# main_board.net
KiCad netlist of a schematic drawn in Altium Designer
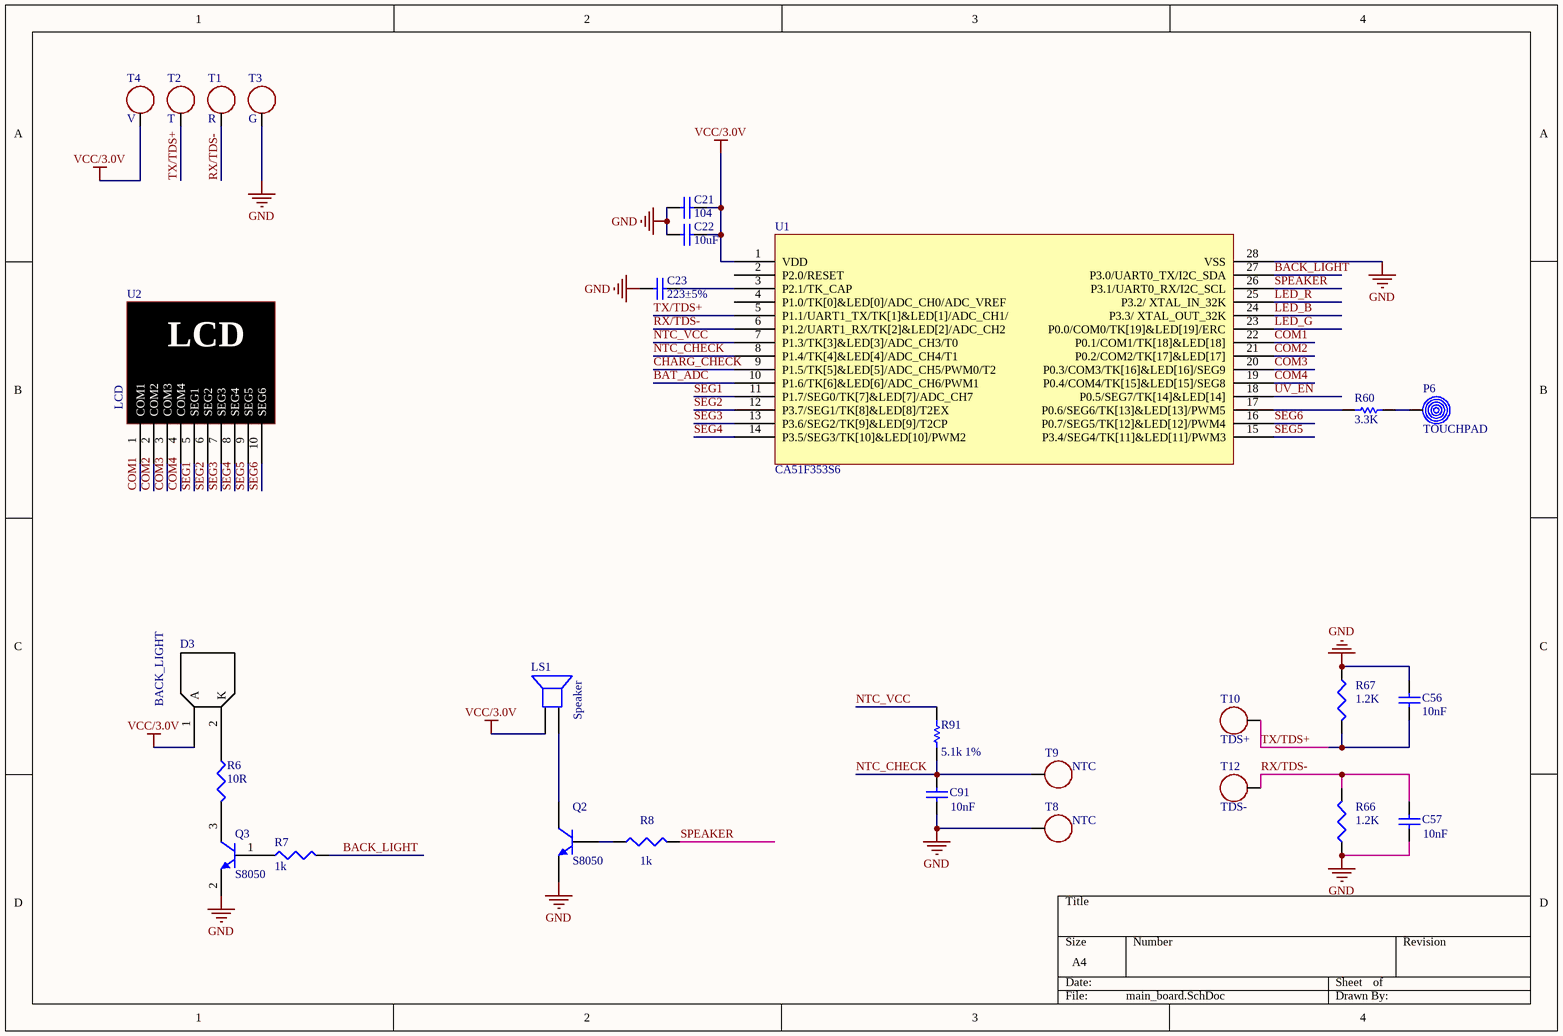
[diagram p0: main_board.SchDoc]

(export (version "E")
  (design (tool "Eeschema 10.0.6"))
  (components
    (comp (ref "C21")
      (value "104")
      (footprint "C0402")
      (description "电容")
      (fields (field (name "Comment") "Cap") (field (name "PUBLISHER") "Altium Limited"))
      (libsource (lib "Miscellaneous Devices") (part "Cap"))
    )
    (comp (ref "C22")
      (value "10uF")
      (footprint "C0805")
      (description "电容")
      (fields (field (name "Comment") "Cap") (field (name "PUBLISHER") "Altium Limited"))
      (libsource (lib "Miscellaneous Devices") (part "Cap"))
    )
    (comp (ref "C23")
      (value "223±5%")
      (footprint "C0402")
      (description "电容")
      (fields (field (name "Comment") "Cap") (field (name "PUBLISHER") "Altium Limited"))
      (libsource (lib "Miscellaneous Devices") (part "Cap"))
    )
    (comp (ref "C56")
      (value "10nF")
      (footprint "C0402")
      (description "电容")
      (fields (field (name "Comment") "Cap") (field (name "PUBLISHER") "Altium Limited"))
      (libsource (lib "altium-import") (part "root_3_Cap_"))
    )
    (comp (ref "C57")
      (value "10nF")
      (footprint "C0402")
      (description "电容")
      (fields (field (name "Comment") "Cap") (field (name "PUBLISHER") "Altium Limited"))
      (libsource (lib "altium-import") (part "root_1_Cap_"))
    )
    (comp (ref "C91")
      (value "10nF")
      (footprint "C0402")
      (description "电容")
      (fields (field (name "Comment") "Cap") (field (name "PUBLISHER") "Altium Limited"))
      (libsource (lib "Miscellaneous Devices") (part "Cap"))
    )
    (comp (ref "D3")
      (value "BACK_LIGHT")
      (footprint "BACK_LIGHT")
      (description "LCD背光")
      (libsource (lib "R1_sch") (part "BACK_LIGHT"))
    )
    (comp (ref "LS1")
      (value "Speaker")
      (footprint "SPEAK")
      (description "蜂鸣器")
      (fields (field (name "PUBLISHER") "Altium Limited"))
      (libsource (lib "Miscellaneous Devices") (part "Speaker"))
    )
    (comp (ref "P6")
      (value "TOUCHPAD")
      (footprint "TP2MMAAA")
      (description "触摸弹簧")
      (libsource (lib "shajunbei") (part "TOUCHPAD"))
    )
    (comp (ref "Q2")
      (value "S8050")
      (footprint "SOT23")
      (description "三极管")
      (libsource (lib "R1_sch") (part "S8050"))
    )
    (comp (ref "Q3")
      (value "S8050")
      (footprint "SOT23")
      (description "三极管")
      (libsource (lib "") (part "S8050_1"))
    )
    (comp (ref "R6")
      (value "10R")
      (footprint "R0402")
      (description "电阻")
      (fields (field (name "Comment") "1.2k") (field (name "PUBLISHER") "Altium Limited"))
      (libsource (lib "Miscellaneous Devices") (part "Res3"))
    )
    (comp (ref "R7")
      (value "1k")
      (footprint "R0402")
      (description "电阻")
      (fields (field (name "Comment") "1.2k") (field (name "PUBLISHER") "Altium Limited"))
      (libsource (lib "Miscellaneous Devices") (part "Res3"))
    )
    (comp (ref "R8")
      (value "1k")
      (footprint "R0402")
      (description "电阻")
      (fields (field (name "Comment") "1.2k") (field (name "PUBLISHER") "Altium Limited"))
      (libsource (lib "Miscellaneous Devices") (part "Res3"))
    )
    (comp (ref "R60")
      (value "3.3K")
      (footprint "R0402")
      (description "电阻")
      (fields (field (name "Comment") "Res1") (field (name "PUBLISHER") "Altium Limited"))
      (libsource (lib "Miscellaneous Devices") (part "Res1"))
    )
    (comp (ref "R66")
      (value "1.2K")
      (footprint "R0402")
      (description "电阻")
      (fields (field (name "Comment") "1.2k") (field (name "PUBLISHER") "Altium Limited"))
      (libsource (lib "Miscellaneous Devices") (part "Res3"))
    )
    (comp (ref "R67")
      (value "1.2K")
      (footprint "R0402")
      (description "电阻")
      (fields (field (name "Comment") "1.2k") (field (name "PUBLISHER") "Altium Limited"))
      (libsource (lib "Miscellaneous Devices") (part "Res3"))
    )
    (comp (ref "R91")
      (value "5.1k 1%")
      (footprint "R0402")
      (description "电阻")
      (fields (field (name "Comment") "Res1") (field (name "PUBLISHER") "Altium Limited"))
      (libsource (lib "Miscellaneous Devices") (part "Res1"))
    )
    (comp (ref "T1")
      (value "R")
      (footprint "TP1_3MMD")
      (description "烧录点Rx")
      (libsource (lib "shajunbei") (part "TEST"))
    )
    (comp (ref "T2")
      (value "T")
      (footprint "TP1_3MMD")
      (description "烧录点Tx")
      (libsource (lib "shajunbei") (part "TEST"))
    )
    (comp (ref "T3")
      (value "G")
      (footprint "TP1_3MMD")
      (description "烧录点GND")
      (libsource (lib "shajunbei") (part "TEST"))
    )
    (comp (ref "T4")
      (value "V")
      (footprint "TP1_3MMD")
      (description "烧录点VCC")
      (libsource (lib "shajunbei") (part "TEST"))
    )
    (comp (ref "T8")
      (value "NTC")
      (footprint "TP1_3MMD")
      (description "NTC焊点")
      (libsource (lib "shajunbei") (part "TEST"))
    )
    (comp (ref "T9")
      (value "NTC")
      (footprint "TP1_3MMD")
      (description "NTC焊点")
      (libsource (lib "shajunbei") (part "TEST"))
    )
    (comp (ref "T10")
      (value "TDS+")
      (footprint "TP1_3MMD")
      (description "TDS焊点")
      (libsource (lib "shajunbei") (part "TEST"))
    )
    (comp (ref "T12")
      (value "TDS-")
      (footprint "TP1_3MMD")
      (description "TDS焊点")
      (libsource (lib "shajunbei") (part "TEST"))
    )
    (comp (ref "U1")
      (value "CA51F353S6")
      (footprint "CA51F35S6-SOP28")
      (description "主控IC")
      (libsource (lib "shajunbei") (part "CA51F353S6"))
    )
    (comp (ref "U2")
      (value "LCD")
      (footprint "LCD_DISPLAY")
      (description "LCD显示屏")
      (libsource (lib "shajunbei") (part "LCD"))
    )
  )
  (nets
    (net (code "1") (name "/BACK_LIGHT") (class "Default")
      (node (ref "R7") (pin "2") (pinfunction "2_2") (pintype "passive"))
      (node (ref "U1") (pin "27") (pinfunction "P3.0/UART0_TX/I2C_SDA_27") (pintype "passive"))
    )
    (net (code "2") (name "/BAT_ADC") (class "Default")
      (node (ref "U1") (pin "10") (pinfunction "P1.6/TK[6]&LED[6]/ADC_CH6/PWM1_10") (pintype "passive"))
    )
    (net (code "3") (name "/CHARG_CHECK") (class "Default")
      (node (ref "U1") (pin "9") (pinfunction "P1.5/TK[5]&LED[5]/ADC_CH5/PWM0/T2_9") (pintype "passive"))
    )
    (net (code "4") (name "/COM1") (class "Default")
      (node (ref "U1") (pin "22") (pinfunction "P0.1/COM1/TK[18]&LED[18]_22") (pintype "passive"))
      (node (ref "U2") (pin "1") (pinfunction "COM1_1") (pintype "passive"))
    )
    (net (code "5") (name "/COM2") (class "Default")
      (node (ref "U1") (pin "21") (pinfunction "P0.2/COM2/TK[17]&LED[17]_21") (pintype "passive"))
      (node (ref "U2") (pin "2") (pinfunction "COM2_2") (pintype "passive"))
    )
    (net (code "6") (name "/COM3") (class "Default")
      (node (ref "U1") (pin "20") (pinfunction "P0.3/COM3/TK[16]&LED[16]/SEG9_20") (pintype "passive"))
      (node (ref "U2") (pin "3") (pinfunction "COM3_3") (pintype "passive"))
    )
    (net (code "7") (name "/COM4") (class "Default")
      (node (ref "U1") (pin "19") (pinfunction "P0.4/COM4/TK[15]&LED[15]/SEG8_19") (pintype "passive"))
      (node (ref "U2") (pin "4") (pinfunction "COM4_4") (pintype "passive"))
    )
    (net (code "8") (name "/LED_B") (class "Default")
      (node (ref "U1") (pin "24") (pinfunction "P3.3/_XTAL_OUT_32K_24") (pintype "passive"))
    )
    (net (code "9") (name "/LED_G") (class "Default")
      (node (ref "U1") (pin "23") (pinfunction "P0.0/COM0/TK[19]&LED[19]/ERC_23") (pintype "passive"))
    )
    (net (code "10") (name "/LED_R") (class "Default")
      (node (ref "U1") (pin "25") (pinfunction "P3.2/_XTAL_IN_32K_25") (pintype "passive"))
    )
    (net (code "11") (name "/NTC_CHECK") (class "Default")
      (node (ref "C91") (pin "2") (pinfunction "2_2") (pintype "passive"))
      (node (ref "R91") (pin "1") (pinfunction "1_1") (pintype "passive"))
      (node (ref "T9") (pin "1") (pinfunction "TOUCHPAD_1") (pintype "passive"))
      (node (ref "U1") (pin "8") (pinfunction "P1.4/TK[4]&LED[4]/ADC_CH4/T1_8") (pintype "passive"))
    )
    (net (code "12") (name "/NTC_VCC") (class "Default")
      (node (ref "R91") (pin "2") (pinfunction "2_2") (pintype "passive"))
      (node (ref "U1") (pin "7") (pinfunction "P1.3/TK[3]&LED[3]/ADC_CH3/T0_7") (pintype "passive"))
    )
    (net (code "13") (name "/RX{slash}TDS-") (class "Default")
      (node (ref "C57") (pin "2") (pinfunction "2_2") (pintype "passive"))
      (node (ref "R66") (pin "2") (pinfunction "2_2") (pintype "passive"))
      (node (ref "T1") (pin "1") (pinfunction "TOUCHPAD_1") (pintype "passive"))
      (node (ref "T12") (pin "1") (pinfunction "TOUCHPAD_1") (pintype "passive"))
      (node (ref "U1") (pin "6") (pinfunction "P1.2/UART1_RX/TK[2]&LED[2]/ADC_CH2_6") (pintype "passive"))
    )
    (net (code "14") (name "/SEG1") (class "Default")
      (node (ref "U1") (pin "11") (pinfunction "P1.7/SEG0/TK[7]&LED[7]/ADC_CH7_11") (pintype "passive"))
      (node (ref "U2") (pin "5") (pinfunction "SEG1_5") (pintype "passive"))
    )
    (net (code "15") (name "/SEG2") (class "Default")
      (node (ref "U1") (pin "12") (pinfunction "P3.7/SEG1/TK[8]&LED[8]/T2EX_12") (pintype "passive"))
      (node (ref "U2") (pin "6") (pinfunction "SEG2_6") (pintype "passive"))
    )
    (net (code "16") (name "/SEG3") (class "Default")
      (node (ref "U1") (pin "13") (pinfunction "P3.6/SEG2/TK[9]&LED[9]/T2CP_13") (pintype "passive"))
      (node (ref "U2") (pin "7") (pinfunction "SEG3_7") (pintype "passive"))
    )
    (net (code "17") (name "/SEG4") (class "Default")
      (node (ref "U1") (pin "14") (pinfunction "P3.5/SEG3/TK[10]&LED[10]/PWM2_14") (pintype "passive"))
      (node (ref "U2") (pin "8") (pinfunction "SEG4_8") (pintype "passive"))
    )
    (net (code "18") (name "/SEG5") (class "Default")
      (node (ref "U1") (pin "15") (pinfunction "P3.4/SEG4/TK[11]&LED[11]/PWM3_15") (pintype "passive"))
      (node (ref "U2") (pin "9") (pinfunction "SEG5_9") (pintype "passive"))
    )
    (net (code "19") (name "/SEG6") (class "Default")
      (node (ref "U1") (pin "16") (pinfunction "P0.7/SEG5/TK[12]&LED[12]/PWM4_16") (pintype "passive"))
      (node (ref "U2") (pin "10") (pinfunction "SEG6_10") (pintype "passive"))
    )
    (net (code "20") (name "/SPEAKER") (class "Default")
      (node (ref "R8") (pin "2") (pinfunction "2_2") (pintype "passive"))
      (node (ref "U1") (pin "26") (pinfunction "P3.1/UART0_RX/I2C_SCL_26") (pintype "passive"))
    )
    (net (code "21") (name "/TX{slash}TDS+") (class "Default")
      (node (ref "C56") (pin "2") (pinfunction "2_2") (pintype "passive"))
      (node (ref "R67") (pin "2") (pinfunction "2_2") (pintype "passive"))
      (node (ref "T10") (pin "1") (pinfunction "TOUCHPAD_1") (pintype "passive"))
      (node (ref "T2") (pin "1") (pinfunction "TOUCHPAD_1") (pintype "passive"))
      (node (ref "U1") (pin "5") (pinfunction "P1.1/UART1_TX/TK[1]&LED[1]/ADC_CH1/_5") (pintype "passive"))
    )
    (net (code "22") (name "/UV_EN") (class "Default")
      (node (ref "U1") (pin "18") (pinfunction "P0.5/SEG7/TK[14]&LED[14]_18") (pintype "passive"))
    )
    (net (code "23") (name "GND") (class "Default")
      (node (ref "C21") (pin "1") (pinfunction "1_1") (pintype "passive"))
      (node (ref "C22") (pin "1") (pinfunction "1_1") (pintype "passive"))
      (node (ref "C23") (pin "1") (pinfunction "1_1") (pintype "passive"))
      (node (ref "C56") (pin "1") (pinfunction "1_1") (pintype "passive"))
      (node (ref "C57") (pin "1") (pinfunction "1_1") (pintype "passive"))
      (node (ref "C91") (pin "1") (pinfunction "1_1") (pintype "passive"))
      (node (ref "Q2") (pin "2") (pinfunction "E_2") (pintype "passive"))
      (node (ref "Q3") (pin "2") (pinfunction "E_2") (pintype "passive"))
      (node (ref "R66") (pin "1") (pinfunction "1_1") (pintype "passive"))
      (node (ref "R67") (pin "1") (pinfunction "1_1") (pintype "passive"))
      (node (ref "T3") (pin "1") (pinfunction "TOUCHPAD_1") (pintype "passive"))
      (node (ref "T8") (pin "1") (pinfunction "TOUCHPAD_1") (pintype "passive"))
      (node (ref "U1") (pin "28") (pinfunction "VSS_28") (pintype "passive"))
    )
    (net (code "24") (name "Net-(D3-K)") (class "Default")
      (node (ref "D3") (pin "2") (pinfunction "K_2") (pintype "passive"))
      (node (ref "R6") (pin "1") (pinfunction "1_1") (pintype "passive"))
    )
    (net (code "25") (name "Net-(P6-TOUCHPAD)") (class "Default")
      (node (ref "P6") (pin "1") (pinfunction "TOUCHPAD_1") (pintype "passive"))
      (node (ref "R60") (pin "1") (pinfunction "1_1") (pintype "passive"))
    )
    (net (code "26") (name "Net-(Q2-B)") (class "Default")
      (node (ref "Q2") (pin "1") (pinfunction "B_1") (pintype "passive"))
      (node (ref "R8") (pin "1") (pinfunction "1_1") (pintype "passive"))
    )
    (net (code "27") (name "Net-(Q2-C)") (class "Default")
      (node (ref "LS1") (pin "2") (pinfunction "2_2") (pintype "passive"))
      (node (ref "Q2") (pin "3") (pinfunction "C_3") (pintype "passive"))
    )
    (net (code "28") (name "Net-(Q3-B)") (class "Default")
      (node (ref "Q3") (pin "1") (pinfunction "B_1") (pintype "passive"))
      (node (ref "R7") (pin "1") (pinfunction "1_1") (pintype "passive"))
    )
    (net (code "29") (name "Net-(Q3-C)") (class "Default")
      (node (ref "Q3") (pin "3") (pinfunction "C_3") (pintype "passive"))
      (node (ref "R6") (pin "2") (pinfunction "2_2") (pintype "passive"))
    )
    (net (code "30") (name "Net-(U1-P0.6{slash}SEG6{slash}TK[13]&LED[13]{slash}PWM5)") (class "Default")
      (node (ref "R60") (pin "2") (pinfunction "2_2") (pintype "passive"))
      (node (ref "U1") (pin "17") (pinfunction "P0.6/SEG6/TK[13]&LED[13]/PWM5_17") (pintype "passive"))
    )
    (net (code "31") (name "Net-(U1-P2.1{slash}TK_CAP)") (class "Default")
      (node (ref "C23") (pin "2") (pinfunction "2_2") (pintype "passive"))
      (node (ref "U1") (pin "3") (pinfunction "P2.1/TK_CAP_3") (pintype "passive"))
    )
    (net (code "32") (name "VCC{slash}3.0V") (class "Default")
      (node (ref "C21") (pin "2") (pinfunction "2_2") (pintype "passive"))
      (node (ref "C22") (pin "2") (pinfunction "2_2") (pintype "passive"))
      (node (ref "D3") (pin "1") (pinfunction "A_1") (pintype "passive"))
      (node (ref "LS1") (pin "1") (pinfunction "1_1") (pintype "passive"))
      (node (ref "T4") (pin "1") (pinfunction "TOUCHPAD_1") (pintype "passive"))
      (node (ref "U1") (pin "1") (pinfunction "VDD_1") (pintype "passive"))
    )
    (net (code "33") (name "unconnected-(U1-P1.0{slash}TK[0]&LED[0]{slash}ADC_CH0{slash}ADC_VREF-Pad4)") (class "Default")
      (node (ref "U1") (pin "4") (pinfunction "P1.0/TK[0]&LED[0]/ADC_CH0/ADC_VREF_4") (pintype "passive"))
    )
    (net (code "34") (name "unconnected-(U1-P2.0{slash}RESET-Pad2)") (class "Default")
      (node (ref "U1") (pin "2") (pinfunction "P2.0/RESET_2") (pintype "passive"))
    )
  )
)
